# TESTED_Midi2PO_V3.net
KiCad netlist of a schematic drawn in EAGLE
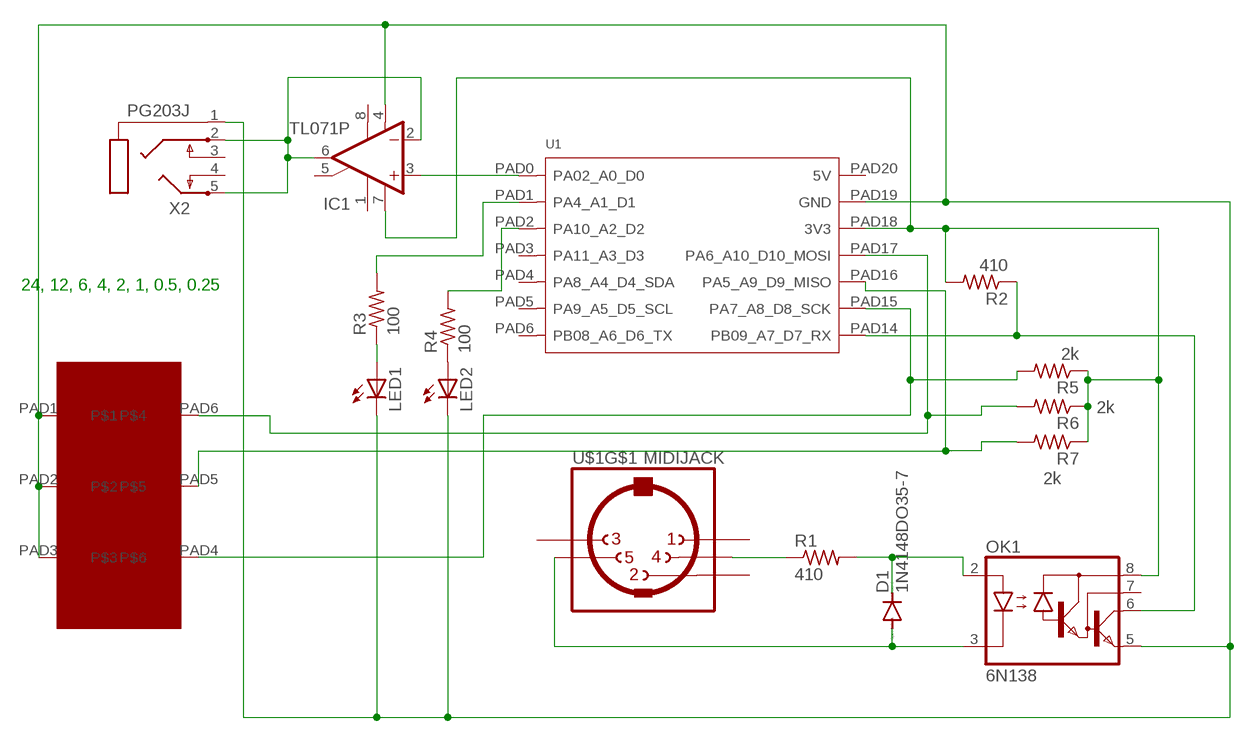
[diagram p0: schematic, sheet 1]

(export (version "E")
  (design (tool "Eeschema 10.0.6"))
  (components
    (comp (ref "D1")
      (value "1N4148DO35-7")
      (footprint "eagle-import:DO35-7")
      (libsource (lib "eagle-import") (part "1N4148DO35-7"))
    )
    (comp (ref "IC1")
      (value "TL071P")
      (footprint "eagle-import:DIL08")
      (libsource (lib "eagle-import") (part "TL071P"))
    )
    (comp (ref "LED1")
      (value "LED5MM")
      (footprint "eagle-import:LED5MM")
      (fields (field (name "SPICEPREFIX") "L"))
      (libsource (lib "eagle-import") (part "LED5MM"))
    )
    (comp (ref "LED2")
      (value "LED5MM")
      (footprint "eagle-import:LED5MM")
      (libsource (lib "eagle-import") (part "LED5MM"))
    )
    (comp (ref "OK1")
      (value "6N138")
      (footprint "eagle-import:DIL08")
      (fields (field (name "MF") "VISHAY/TELEFUNKEN"))
      (libsource (lib "eagle-import") (part "6N138"))
    )
    (comp (ref "R1")
      (value "410")
      (footprint "eagle-import:0207_9")
      (libsource (lib "eagle-import") (part "R-US_0207/9"))
    )
    (comp (ref "R2")
      (value "410")
      (footprint "eagle-import:0207_9")
      (libsource (lib "eagle-import") (part "R-US_0207/9"))
    )
    (comp (ref "R3")
      (value "100")
      (footprint "eagle-import:0207_9")
      (fields (field (name "SPICEPREFIX") "R"))
      (libsource (lib "eagle-import") (part "R-US_0207/9"))
    )
    (comp (ref "R4")
      (value "100")
      (footprint "eagle-import:0207_9")
      (libsource (lib "eagle-import") (part "R-US_0207/9"))
    )
    (comp (ref "R5")
      (value "2k")
      (footprint "eagle-import:0207_9")
      (libsource (lib "eagle-import") (part "R-US_0207/9"))
    )
    (comp (ref "R6")
      (value "2k")
      (footprint "eagle-import:0207_9")
      (libsource (lib "eagle-import") (part "R-US_0207/9"))
    )
    (comp (ref "R7")
      (value "2k")
      (footprint "eagle-import:0207_9")
      (libsource (lib "eagle-import") (part "R-US_0207/9"))
    )
    (comp (ref "U$1")
      (value "MIDIJACK")
      (footprint "eagle-import:CP-2350")
      (libsource (lib "eagle-import") (part "MIDIJACK"))
    )
    (comp (ref "U$2")
      (value "MCNDA-03V")
      (footprint "eagle-import:MCNDA-03V")
      (libsource (lib "eagle-import") (part "MCNDA-03V"))
    )
    (comp (ref "U1")
      (value "MOUDLE-SEEEDUINO-XIAO")
      (footprint "eagle-import:MOUDLE14P-2.54-21X17.8MM")
      (libsource (lib "eagle-import") (part "MOUDLE-SEEEDUINO-XIAO"))
    )
    (comp (ref "X2")
      (value "PG203J")
      (footprint "eagle-import:PG203J")
      (libsource (lib "eagle-import") (part "PG203J"))
    )
  )
  (nets
    (net (code "1") (name "Net-(IC1-+IN)") (class "Default")
      (node (ref "IC1") (pin "3") (pinfunction "+IN_3") (pintype "input"))
      (node (ref "U1") (pin "PAD0") (pinfunction "PA02_A0_D0_PAD0") (pintype "bidirectional"))
    )
    (net (code "2") (name "Net-(IC1--IN)") (class "Default")
      (node (ref "IC1") (pin "2") (pinfunction "-IN_2") (pintype "input"))
      (node (ref "IC1") (pin "6") (pinfunction "OUT_6") (pintype "output"))
      (node (ref "X2") (pin "2") (pinfunction "2_2") (pintype "passive"))
      (node (ref "X2") (pin "5") (pinfunction "5_5") (pintype "passive"))
    )
    (net (code "3") (name "Net-(IC1-V+)") (class "Default")
      (node (ref "IC1") (pin "7") (pinfunction "V+_7") (pintype "power_in"))
      (node (ref "OK1") (pin "8") (pinfunction "VCC_8") (pintype "passive"))
      (node (ref "R2") (pin "2") (pinfunction "2_2") (pintype "passive"))
      (node (ref "R5") (pin "1") (pinfunction "1_1") (pintype "passive"))
      (node (ref "R6") (pin "1") (pinfunction "1_1") (pintype "passive"))
      (node (ref "R7") (pin "1") (pinfunction "1_1") (pintype "passive"))
      (node (ref "U1") (pin "PAD18") (pinfunction "3V3_PAD18") (pintype "bidirectional"))
    )
    (net (code "4") (name "Net-(IC1-V-)") (class "Default")
      (node (ref "IC1") (pin "4") (pinfunction "V-_4") (pintype "power_in"))
      (node (ref "LED1") (pin "K") (pinfunction "C_K") (pintype "passive"))
      (node (ref "LED2") (pin "K") (pinfunction "C_K") (pintype "passive"))
      (node (ref "OK1") (pin "5") (pinfunction "GND_5") (pintype "passive"))
      (node (ref "U$2") (pin "PAD1") (pinfunction "P$1_PAD1") (pintype "bidirectional"))
      (node (ref "U$2") (pin "PAD2") (pinfunction "P$2_PAD2") (pintype "bidirectional"))
      (node (ref "U$2") (pin "PAD3") (pinfunction "P$3_PAD3") (pintype "bidirectional"))
      (node (ref "U1") (pin "PAD19") (pinfunction "GND_PAD19") (pintype "bidirectional"))
      (node (ref "X2") (pin "1") (pinfunction "1_1") (pintype "passive"))
    )
    (net (code "5") (name "Net-(LED1-PadA)") (class "Default")
      (node (ref "LED1") (pin "A") (pinfunction "A_A") (pintype "passive"))
      (node (ref "R3") (pin "1") (pinfunction "1_1") (pintype "passive"))
    )
    (net (code "6") (name "Net-(LED2-PadA)") (class "Default")
      (node (ref "LED2") (pin "A") (pinfunction "A_A") (pintype "passive"))
      (node (ref "R4") (pin "1") (pinfunction "1_1") (pintype "passive"))
    )
    (net (code "7") (name "Net-(OK1-A)") (class "Default")
      (node (ref "D1") (pin "C") (pinfunction "C_C") (pintype "passive"))
      (node (ref "OK1") (pin "2") (pinfunction "A_2") (pintype "passive"))
      (node (ref "R1") (pin "2") (pinfunction "2_2") (pintype "passive"))
    )
    (net (code "8") (name "Net-(OK1-C)") (class "Default")
      (node (ref "D1") (pin "A") (pinfunction "A_A") (pintype "passive"))
      (node (ref "OK1") (pin "3") (pinfunction "C_3") (pintype "passive"))
      (node (ref "U$1") (pin "5") (pinfunction "5_5") (pintype "passive"))
    )
    (net (code "9") (name "Net-(OK1-VO)") (class "Default")
      (node (ref "OK1") (pin "6") (pinfunction "VO_6") (pintype "passive"))
      (node (ref "R2") (pin "1") (pinfunction "1_1") (pintype "passive"))
      (node (ref "U1") (pin "PAD14") (pinfunction "PB09_A7_D7_RX_PAD14") (pintype "bidirectional"))
    )
    (net (code "10") (name "Net-(R1-Pad1)") (class "Default")
      (node (ref "R1") (pin "1") (pinfunction "1_1") (pintype "passive"))
      (node (ref "U$1") (pin "4") (pinfunction "4_4") (pintype "passive"))
    )
    (net (code "11") (name "Net-(U$2-P$4)") (class "Default")
      (node (ref "R6") (pin "2") (pinfunction "2_2") (pintype "passive"))
      (node (ref "U$2") (pin "PAD6") (pinfunction "P$4_PAD6") (pintype "bidirectional"))
      (node (ref "U1") (pin "PAD17") (pinfunction "PA6_A10_D10_MOSI_PAD17") (pintype "bidirectional"))
    )
    (net (code "12") (name "Net-(U$2-P$5)") (class "Default")
      (node (ref "R7") (pin "2") (pinfunction "2_2") (pintype "passive"))
      (node (ref "U$2") (pin "PAD5") (pinfunction "P$5_PAD5") (pintype "bidirectional"))
      (node (ref "U1") (pin "PAD16") (pinfunction "PA5_A9_D9_MISO_PAD16") (pintype "bidirectional"))
    )
    (net (code "13") (name "Net-(U$2-P$6)") (class "Default")
      (node (ref "R5") (pin "2") (pinfunction "2_2") (pintype "passive"))
      (node (ref "U$2") (pin "PAD4") (pinfunction "P$6_PAD4") (pintype "bidirectional"))
      (node (ref "U1") (pin "PAD15") (pinfunction "PA7_A8_D8_SCK_PAD15") (pintype "bidirectional"))
    )
    (net (code "14") (name "Net-(U1-PA4_A1_D1)") (class "Default")
      (node (ref "R3") (pin "2") (pinfunction "2_2") (pintype "passive"))
      (node (ref "U1") (pin "PAD1") (pinfunction "PA4_A1_D1_PAD1") (pintype "bidirectional"))
    )
    (net (code "15") (name "Net-(U1-PA10_A2_D2)") (class "Default")
      (node (ref "R4") (pin "2") (pinfunction "2_2") (pintype "passive"))
      (node (ref "U1") (pin "PAD2") (pinfunction "PA10_A2_D2_PAD2") (pintype "bidirectional"))
    )
    (net (code "16") (name "unconnected-(IC1-ON1-Pad1)") (class "Default")
      (node (ref "IC1") (pin "1") (pinfunction "ON1_1") (pintype "passive"))
    )
    (net (code "17") (name "unconnected-(IC1-ON2-Pad5)") (class "Default")
      (node (ref "IC1") (pin "5") (pinfunction "ON2_5") (pintype "passive"))
    )
    (net (code "18") (name "unconnected-(IC1-OPT-Pad8)") (class "Default")
      (node (ref "IC1") (pin "8") (pinfunction "OPT_8") (pintype "passive"))
    )
    (net (code "19") (name "unconnected-(OK1-VB-Pad7)") (class "Default")
      (node (ref "OK1") (pin "7") (pinfunction "VB_7") (pintype "passive"))
    )
    (net (code "20") (name "unconnected-(U$1-Pad1)") (class "Default")
      (node (ref "U$1") (pin "1") (pinfunction "1_1") (pintype "passive"))
    )
    (net (code "21") (name "unconnected-(U$1-Pad2)") (class "Default")
      (node (ref "U$1") (pin "2") (pinfunction "2_2") (pintype "passive"))
    )
    (net (code "22") (name "unconnected-(U$1-Pad3)") (class "Default")
      (node (ref "U$1") (pin "3") (pinfunction "3_3") (pintype "passive"))
    )
    (net (code "23") (name "unconnected-(U1-5V-PadPAD20)") (class "Default")
      (node (ref "U1") (pin "PAD20") (pinfunction "5V_PAD20") (pintype "bidirectional"))
    )
    (net (code "24") (name "unconnected-(U1-PA8_A4_D4_SDA-PadPAD4)") (class "Default")
      (node (ref "U1") (pin "PAD4") (pinfunction "PA8_A4_D4_SDA_PAD4") (pintype "bidirectional"))
    )
    (net (code "25") (name "unconnected-(U1-PA9_A5_D5_SCL-PadPAD5)") (class "Default")
      (node (ref "U1") (pin "PAD5") (pinfunction "PA9_A5_D5_SCL_PAD5") (pintype "bidirectional"))
    )
    (net (code "26") (name "unconnected-(U1-PA11_A3_D3-PadPAD3)") (class "Default")
      (node (ref "U1") (pin "PAD3") (pinfunction "PA11_A3_D3_PAD3") (pintype "bidirectional"))
    )
    (net (code "27") (name "unconnected-(U1-PB08_A6_D6_TX-PadPAD6)") (class "Default")
      (node (ref "U1") (pin "PAD6") (pinfunction "PB08_A6_D6_TX_PAD6") (pintype "bidirectional"))
    )
    (net (code "28") (name "unconnected-(X2-Pad3)") (class "Default")
      (node (ref "X2") (pin "3") (pinfunction "3_3") (pintype "passive"))
    )
    (net (code "29") (name "unconnected-(X2-Pad4)") (class "Default")
      (node (ref "X2") (pin "4") (pinfunction "4_4") (pintype "passive"))
    )
  )
)
